# IMX7S_POWER.net
KiCad netlist of a schematic drawn in Altium Designer
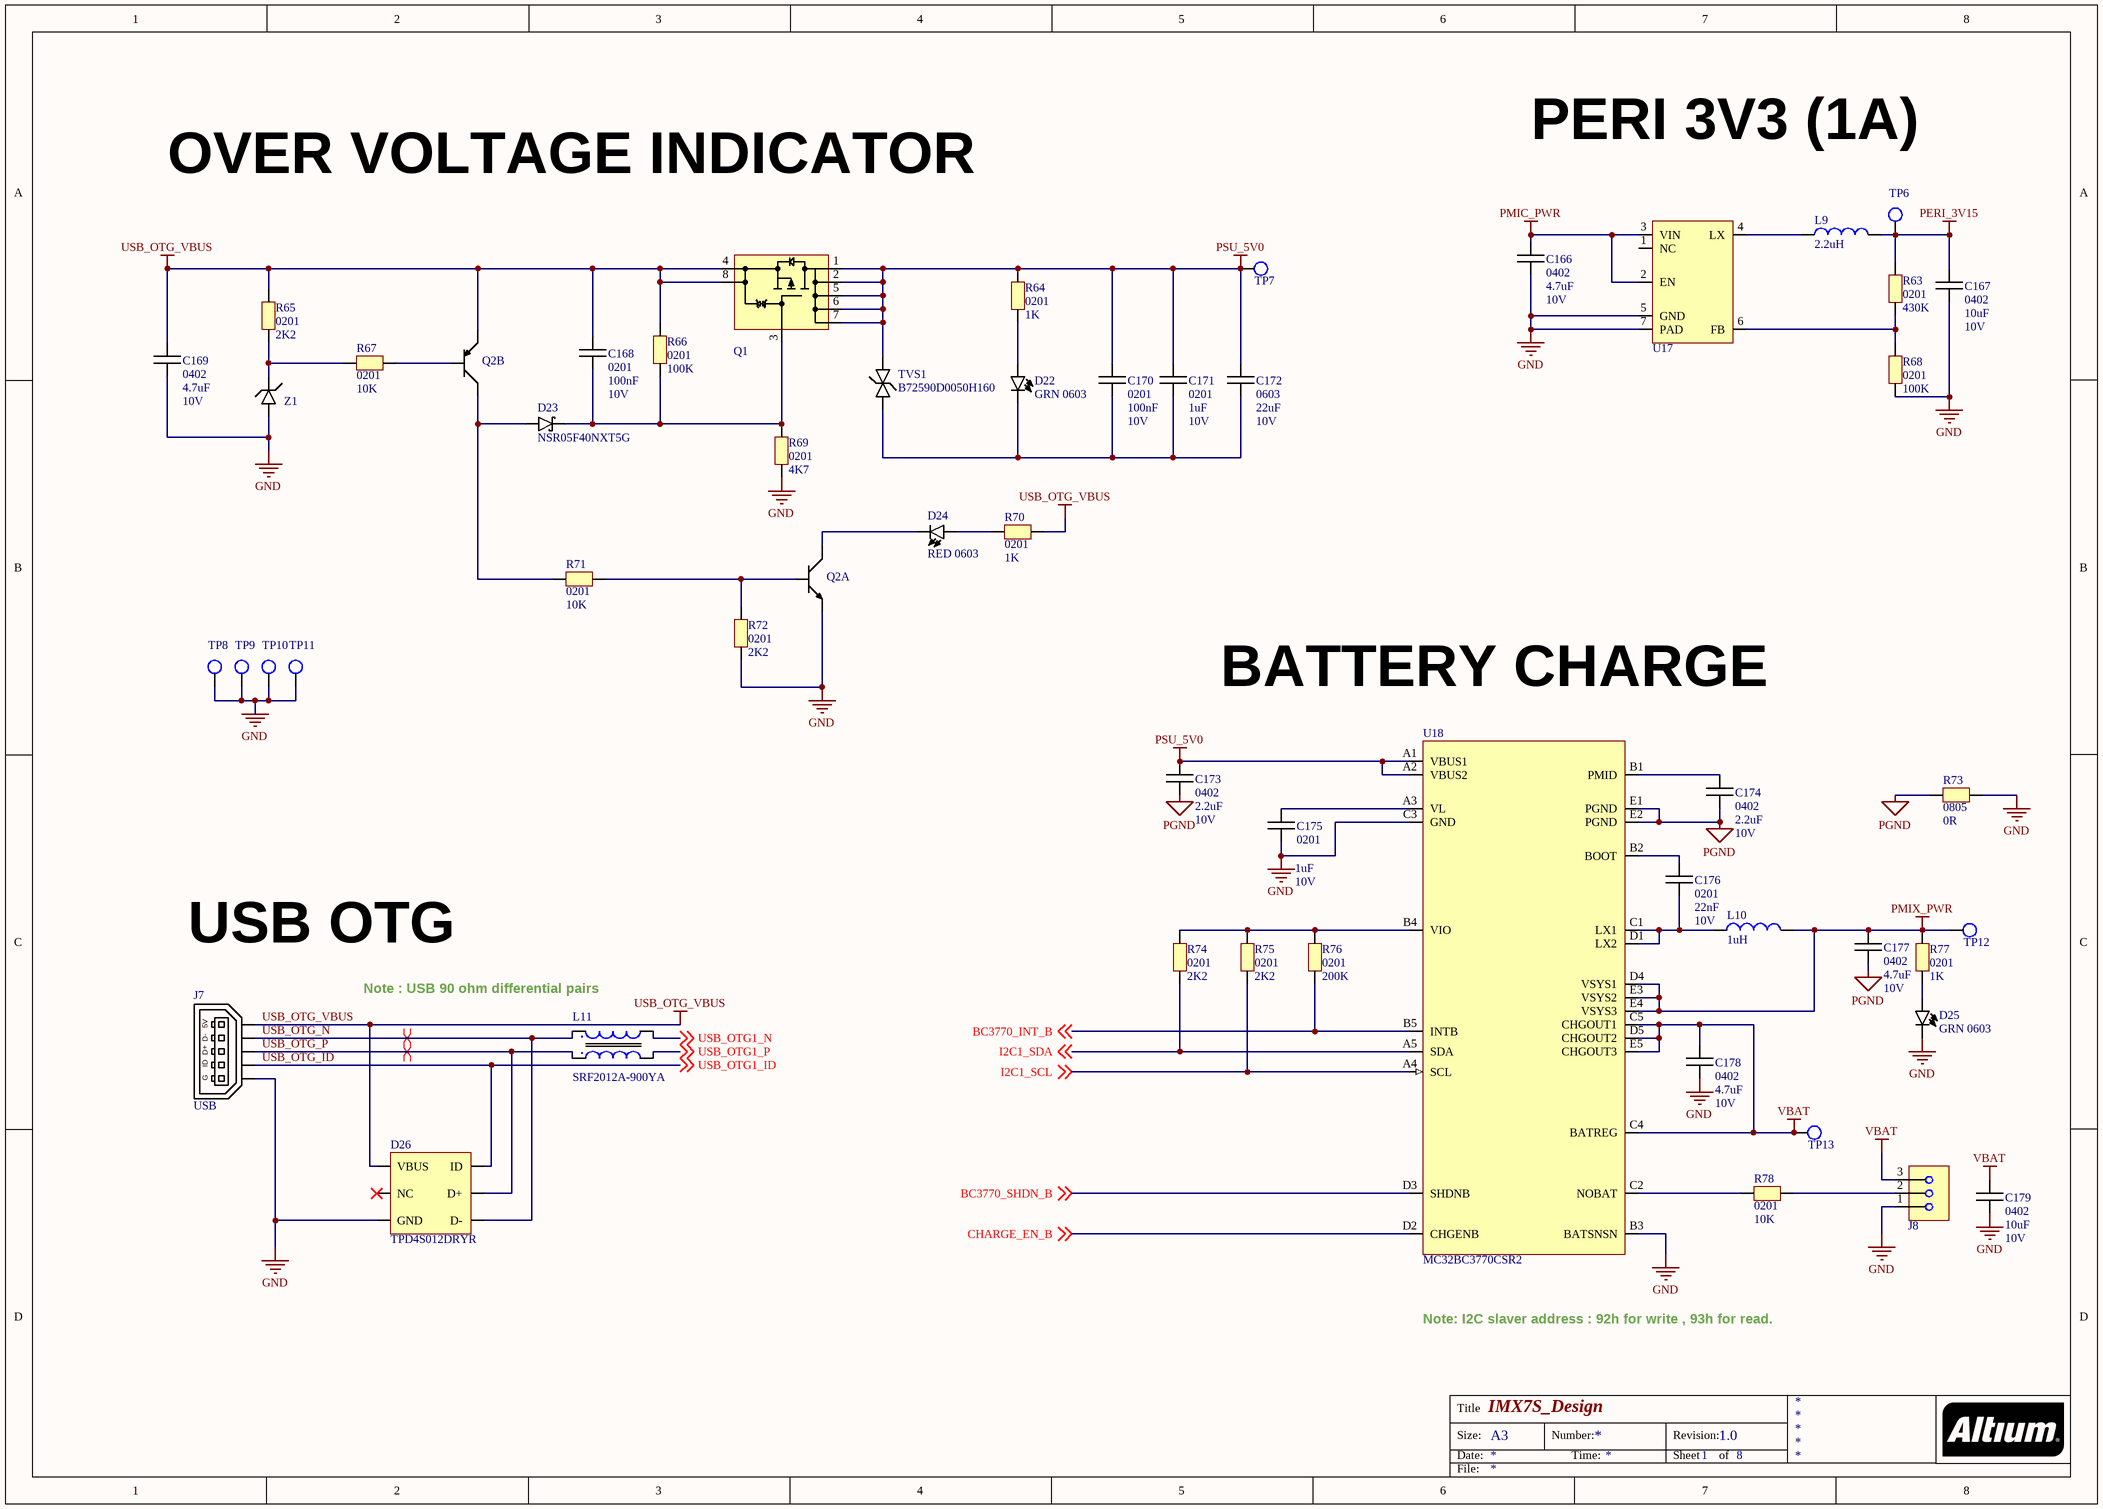
[diagram p0: IMX7S_POWER.SchDoc]

(export (version "E")
  (design (tool "Eeschema 10.0.6"))
  (components
    (comp (ref "C166")
      (value "4.7uF")
      (footprint "C0402")
      (fields (field (name "PACKAGE") "0402") (field (name "VOLTAGE") "10V") (field (name "Comment") "C0402"))
      (libsource (lib "Schlib_IMX7") (part "C0402"))
    )
    (comp (ref "C167")
      (value "10uF")
      (footprint "C0402")
      (description "Smd Multilayer Ceramic Capacitor, Grm Series, 10 F, 20%, X5r, 6.3 V, 0402 [1005 Metric]")
      (fields
        (field (name "PACKAGE") "0402")
        (field (name "VOLTAGE") "10V")
        (field (name "TOLERANCE") "20%")
        (field (name "Comment") "C0402")
      )
      (libsource (lib "Schlib_IMX7") (part "C0402"))
    )
    (comp (ref "C168")
      (value "100nF")
      (footprint "C0201")
      (fields
        (field (name "PACKAGE") "0201")
        (field (name "VOLTAGE") "10V")
        (field (name "TOLERANCE") "10%")
        (field (name "Comment") "C0201")
      )
      (libsource (lib "Schlib_IMX7") (part "C0201"))
    )
    (comp (ref "C169")
      (value "4.7uF")
      (footprint "C0402")
      (fields (field (name "PACKAGE") "0402") (field (name "VOLTAGE") "10V") (field (name "Comment") "C0402"))
      (libsource (lib "Schlib_IMX7") (part "C0402"))
    )
    (comp (ref "C170")
      (value "100nF")
      (footprint "C0201")
      (fields
        (field (name "PACKAGE") "0201")
        (field (name "VOLTAGE") "10V")
        (field (name "TOLERANCE") "10%")
        (field (name "Comment") "C0201")
      )
      (libsource (lib "Schlib_IMX7") (part "C0201"))
    )
    (comp (ref "C171")
      (value "1uF")
      (footprint "C0201")
      (description "CAP CER 1UF 6.3V X5R 0201")
      (fields
        (field (name "PACKAGE") "0201")
        (field (name "VOLTAGE") "10V")
        (field (name "TOLERANCE") "20%")
        (field (name "Comment") "C0201")
      )
      (libsource (lib "Schlib_IMX7") (part "C0201"))
    )
    (comp (ref "C172")
      (value "22uF")
      (footprint "C0603")
      (description "Cap Ceramic 22uF 6.3V X5R 20% SMD 0603 85C Paper T/R")
      (fields
        (field (name "PACKAGE") "0603")
        (field (name "VOLTAGE") "10V")
        (field (name "TOLERANCE") "20%")
        (field (name "Comment") "C0603")
      )
      (libsource (lib "Schlib_IMX7") (part "C0603"))
    )
    (comp (ref "C173")
      (value "2.2uF")
      (footprint "C0402")
      (fields
        (field (name "PACKAGE") "0402")
        (field (name "VOLTAGE") "10V")
        (field (name "TOLERANCE") "20%")
        (field (name "Comment") "C0402")
      )
      (libsource (lib "Schlib_IMX7") (part "C0402"))
    )
    (comp (ref "C174")
      (value "2.2uF")
      (footprint "C0402")
      (fields
        (field (name "PACKAGE") "0402")
        (field (name "VOLTAGE") "10V")
        (field (name "TOLERANCE") "20%")
        (field (name "Comment") "C0402")
      )
      (libsource (lib "Schlib_IMX7") (part "C0402"))
    )
    (comp (ref "C175")
      (value "1uF")
      (footprint "C0201")
      (description "CAP CER 1UF 6.3V X5R 0201")
      (fields
        (field (name "PACKAGE") "0201")
        (field (name "VOLTAGE") "10V")
        (field (name "TOLERANCE") "20%")
        (field (name "Comment") "C0201")
      )
      (libsource (lib "Schlib_IMX7") (part "C0201"))
    )
    (comp (ref "C176")
      (value "22nF")
      (footprint "C0201")
      (description "MULTICOMP - MC0201X223K6R3CT - CAP, 0.022µF, 6.3V, 10%, X5R, 0201")
      (fields
        (field (name "PACKAGE") "0201")
        (field (name "VOLTAGE") "10V")
        (field (name "TOLERANCE") "10%")
        (field (name "Comment") "C0201")
      )
      (libsource (lib "Schlib_IMX7") (part "C0201"))
    )
    (comp (ref "C177")
      (value "4.7uF")
      (footprint "C0402")
      (fields (field (name "PACKAGE") "0402") (field (name "VOLTAGE") "10V") (field (name "Comment") "C0402"))
      (libsource (lib "Schlib_IMX7") (part "C0402"))
    )
    (comp (ref "C178")
      (value "4.7uF")
      (footprint "C0402")
      (fields (field (name "PACKAGE") "0402") (field (name "VOLTAGE") "10V") (field (name "Comment") "C0402"))
      (libsource (lib "Schlib_IMX7") (part "C0402"))
    )
    (comp (ref "C179")
      (value "10uF")
      (footprint "C0402")
      (fields
        (field (name "PACKAGE") "0402")
        (field (name "VOLTAGE") "10V")
        (field (name "TOLERANCE") "20%")
        (field (name "Comment") "C0402")
      )
      (libsource (lib "Schlib_IMX7") (part "C0402"))
    )
    (comp (ref "D22") (value "GRN 0603") (footprint "D0603") (libsource (lib "Schlib_IMX7") (part "LED")))
    (comp (ref "D23")
      (value "NSR05F40NXT5G")
      (footprint "DSN2")
      (libsource (lib "Schlib_IMX7") (part "Shotky"))
    )
    (comp (ref "D24") (value "RED 0603") (footprint "D0603") (libsource (lib "Schlib_IMX7") (part "LED")))
    (comp (ref "D25") (value "GRN 0603") (footprint "D0603") (libsource (lib "Schlib_IMX7") (part "LED")))
    (comp (ref "D26")
      (value "TPD4S012DRYR")
      (footprint "SON6")
      (libsource (lib "Schlib_IMX7") (part "TPD4S012DRYR"))
    )
    (comp (ref "J7") (value "USB") (footprint "MICRO_USB") (libsource (lib "Schlib_IMX7") (part "MICRO_USB")))
    (comp (ref "J8")
      (value "JST_XH_3")
      (footprint "JST-XH")
      (libsource (lib "Schlib_IMX7") (part "JST_XH_3"))
    )
    (comp (ref "L9")
      (value "2.2uH")
      (footprint "SELF")
      (fields (field (name "TOLERANCE") "30%") (field (name "Comment") "Self"))
      (libsource (lib "Schlib_IMX7") (part "Self"))
    )
    (comp (ref "L10")
      (value "1uH")
      (footprint "R0402")
      (fields (field (name "TOLERANCE") "20%") (field (name "Comment") "Self"))
      (libsource (lib "Schlib_IMX7") (part "Self"))
    )
    (comp (ref "L11")
      (value "SRF2012A-900YA")
      (footprint "EMI_SP")
      (libsource (lib "Schlib_IMX7") (part "SRF2012A-900YA"))
    )
    (comp (ref "Q1")
      (value "FDMA530PZ")
      (footprint "MICROFET_2x2")
      (libsource (lib "Schlib_IMX7") (part "FDMA530PZ"))
    )
    (comp (ref "Q2")
      (value "HBDM60V600W-7")
      (footprint "SOT363")
      (libsource (lib "Schlib_IMX7") (part "HBDM60V600W-7"))
    )
    (comp (ref "R63")
      (value "430K")
      (footprint "R0201")
      (description "RES SMD 430K OHM 1% 1/20W 0201")
      (fields (field (name "PACKAGE") "0201") (field (name "VOLTAGE") "0V") (field (name "TOLERANCE") "1%"))
      (libsource (lib "") (part "R0201_1"))
    )
    (comp (ref "R64")
      (value "1K")
      (footprint "R0201")
      (fields
        (field (name "PACKAGE") "0201")
        (field (name "VOLTAGE") "0V")
        (field (name "TOLERANCE") "1%")
        (field (name "Comment") "R0201")
      )
      (libsource (lib "") (part "R0201_1"))
    )
    (comp (ref "R65")
      (value "2K2")
      (footprint "R0201")
      (description "MULTICOMP - MCRE000148 - RES, 2K2, 1%, 0.05W, 0201, THICK FILM")
      (fields (field (name "PACKAGE") "0201") (field (name "VOLTAGE") "0V") (field (name "TOLERANCE") "1%"))
      (libsource (lib "") (part "R0201_1"))
    )
    (comp (ref "R66")
      (value "100K")
      (footprint "R0201")
      (description "MULTICOMP - MCWR02X1003FAL - RES, 100K, 1%, 0.05W, THICK FILM")
      (fields (field (name "PACKAGE") "0201") (field (name "VOLTAGE") "0V") (field (name "TOLERANCE") "1%"))
      (libsource (lib "") (part "R0201_3"))
    )
    (comp (ref "R67")
      (value "10K")
      (footprint "R0201")
      (fields
        (field (name "PACKAGE") "0201")
        (field (name "VOLTAGE") "0V")
        (field (name "TOLERANCE") "1%")
        (field (name "Comment") "R0201")
      )
      (libsource (lib "") (part "R0201_2"))
    )
    (comp (ref "R68")
      (value "100K")
      (footprint "R0201")
      (description "MULTICOMP - MCWR02X1003FAL - RES, 100K, 1%, 0.05W, THICK FILM")
      (fields (field (name "PACKAGE") "0201") (field (name "VOLTAGE") "0V") (field (name "TOLERANCE") "1%"))
      (libsource (lib "") (part "R0201_1"))
    )
    (comp (ref "R69")
      (value "4K7")
      (footprint "R0201")
      (description "RES SMD 4.7K OHM 1% 1/20W 0201")
      (fields (field (name "PACKAGE") "0201") (field (name "VOLTAGE") "0V") (field (name "TOLERANCE") "1%"))
      (libsource (lib "") (part "R0201_3"))
    )
    (comp (ref "R70")
      (value "1K")
      (footprint "R0201")
      (fields
        (field (name "PACKAGE") "0201")
        (field (name "VOLTAGE") "0V")
        (field (name "TOLERANCE") "1%")
        (field (name "Comment") "R0201")
      )
      (libsource (lib "Schlib_IMX7") (part "R0201"))
    )
    (comp (ref "R71")
      (value "10K")
      (footprint "R0201")
      (fields
        (field (name "PACKAGE") "0201")
        (field (name "VOLTAGE") "0V")
        (field (name "TOLERANCE") "1%")
        (field (name "Comment") "R0201")
      )
      (libsource (lib "") (part "R0201_2"))
    )
    (comp (ref "R72")
      (value "2K2")
      (footprint "R0201")
      (description "MULTICOMP - MCRE000148 - RES, 2K2, 1%, 0.05W, 0201, THICK FILM")
      (fields (field (name "PACKAGE") "0201") (field (name "VOLTAGE") "0V") (field (name "TOLERANCE") "1%"))
      (libsource (lib "") (part "R0201_1"))
    )
    (comp (ref "R73")
      (value "0R")
      (footprint "R0805")
      (description "RESISTOR, THICK FILM, JUMPER, 0 OHM, 125mW, 1%")
      (fields (field (name "PACKAGE") "0805") (field (name "VOLTAGE") "0V") (field (name "TOLERANCE") "1%"))
      (libsource (lib "Schlib_IMX7") (part "R0805"))
    )
    (comp (ref "R74")
      (value "2K2")
      (footprint "R0201")
      (description "MULTICOMP - MCRE000148 - RES, 2K2, 1%, 0.05W, 0201, THICK FILM")
      (fields (field (name "PACKAGE") "0201") (field (name "VOLTAGE") "0V") (field (name "TOLERANCE") "1%"))
      (libsource (lib "") (part "R0201_1"))
    )
    (comp (ref "R75")
      (value "2K2")
      (footprint "R0201")
      (description "MULTICOMP - MCRE000148 - RES, 2K2, 1%, 0.05W, 0201, THICK FILM")
      (fields (field (name "PACKAGE") "0201") (field (name "VOLTAGE") "0V") (field (name "TOLERANCE") "1%"))
      (libsource (lib "") (part "R0201_1"))
    )
    (comp (ref "R76")
      (value "200K")
      (footprint "R0201")
      (description "MULTICOMP - MCRE000195 - RES COUCHE EPAISSE 200K 1% 0.05W 0201")
      (fields (field (name "PACKAGE") "0201") (field (name "VOLTAGE") "0V") (field (name "TOLERANCE") "1%"))
      (libsource (lib "") (part "R0201_1"))
    )
    (comp (ref "R77")
      (value "1K")
      (footprint "R0201")
      (fields
        (field (name "PACKAGE") "0201")
        (field (name "VOLTAGE") "0V")
        (field (name "TOLERANCE") "1%")
        (field (name "Comment") "R0201")
      )
      (libsource (lib "") (part "R0201_1"))
    )
    (comp (ref "R78")
      (value "10K")
      (footprint "R0201")
      (fields
        (field (name "PACKAGE") "0201")
        (field (name "VOLTAGE") "0V")
        (field (name "TOLERANCE") "1%")
        (field (name "Comment") "R0201")
      )
      (libsource (lib "") (part "R0201_2"))
    )
    (comp (ref "TP6")
      (value "TestPoint")
      (footprint "TESTPOINT")
      (libsource (lib "Schlib_IMX7") (part "TestPoint"))
    )
    (comp (ref "TP7")
      (value "TestPoint")
      (footprint "TESTPOINT")
      (libsource (lib "Schlib_IMX7") (part "TestPoint"))
    )
    (comp (ref "TP8")
      (value "TestPoint")
      (footprint "TESTPOINT")
      (libsource (lib "Schlib_IMX7") (part "TestPoint"))
    )
    (comp (ref "TP9")
      (value "TestPoint")
      (footprint "TESTPOINT")
      (libsource (lib "Schlib_IMX7") (part "TestPoint"))
    )
    (comp (ref "TP10")
      (value "TestPoint")
      (footprint "TESTPOINT")
      (libsource (lib "Schlib_IMX7") (part "TestPoint"))
    )
    (comp (ref "TP11")
      (value "TestPoint")
      (footprint "TESTPOINT")
      (libsource (lib "Schlib_IMX7") (part "TestPoint"))
    )
    (comp (ref "TP12")
      (value "TestPoint")
      (footprint "TESTPOINT")
      (libsource (lib "Schlib_IMX7") (part "TestPoint"))
    )
    (comp (ref "TP13")
      (value "TestPoint")
      (footprint "TESTPOINT")
      (libsource (lib "Schlib_IMX7") (part "TestPoint"))
    )
    (comp (ref "TVS1")
      (value "B72590D0050H160")
      (footprint "R0402")
      (libsource (lib "Schlib_IMX7") (part "B72590D0050H160"))
    )
    (comp (ref "U17")
      (value "AP3417CDNTR-G1")
      (footprint "DFN2020")
      (libsource (lib "Schlib_IMX7") (part "AP3417CDNTR-G1"))
    )
    (comp (ref "U18")
      (value "MC32BC3770CSR2")
      (footprint "BGA25x5")
      (libsource (lib "Schlib_IMX7") (part "MC32BC3770CSR2"))
    )
    (comp (ref "Z1")
      (value "Zener")
      (footprint "Zener")
      (fields (field (name "TOLERANCE") "2%"))
      (libsource (lib "Schlib_IMX7") (part "Zener"))
    )
  )
  (nets
    (net (code "1") (name "/USB_OTG_N") (class "Default")
      (node (ref "D26") (pin "2") (pinfunction "D-_2") (pintype "passive"))
      (node (ref "J7") (pin "2") (pinfunction "D-_2") (pintype "passive"))
      (node (ref "L11") (pin "1") (pinfunction "1_1") (pintype "passive"))
    )
    (net (code "2") (name "/USB_OTG_P") (class "Default")
      (node (ref "D26") (pin "1") (pinfunction "D+_1") (pintype "passive"))
      (node (ref "J7") (pin "3") (pinfunction "D+_3") (pintype "passive"))
      (node (ref "L11") (pin "4") (pinfunction "4_4") (pintype "passive"))
    )
    (net (code "3") (name "BC3770_INT_B") (class "Default")
      (node (ref "R76") (pin "1") (pinfunction "1_1") (pintype "passive"))
      (node (ref "U18") (pin "B5") (pinfunction "INTB_B5") (pintype "passive"))
    )
    (net (code "4") (name "BC3770_SHDN_B") (class "Default")
      (node (ref "U18") (pin "D3") (pinfunction "SHDNB_D3") (pintype "passive"))
    )
    (net (code "5") (name "CHARGE_EN_B") (class "Default")
      (node (ref "U18") (pin "D2") (pinfunction "CHGENB_D2") (pintype "passive"))
    )
    (net (code "6") (name "GND") (class "Default")
      (node (ref "C166") (pin "2") (pinfunction "2_2") (pintype "passive"))
      (node (ref "C167") (pin "2") (pinfunction "2_2") (pintype "passive"))
      (node (ref "C169") (pin "1") (pinfunction "1_1") (pintype "passive"))
      (node (ref "C175") (pin "1") (pinfunction "1_1") (pintype "passive"))
      (node (ref "C178") (pin "2") (pinfunction "2_2") (pintype "passive"))
      (node (ref "C179") (pin "2") (pinfunction "2_2") (pintype "passive"))
      (node (ref "D25") (pin "2") (pinfunction "K_2") (pintype "passive"))
      (node (ref "D26") (pin "4") (pinfunction "GND_4") (pintype "passive"))
      (node (ref "J7") (pin "5") (pinfunction "GND_5") (pintype "passive"))
      (node (ref "J8") (pin "1") (pintype "passive"))
      (node (ref "Q2") (pin "5") (pinfunction "EQ1_5") (pintype "passive"))
      (node (ref "R68") (pin "1") (pinfunction "1_1") (pintype "passive"))
      (node (ref "R69") (pin "2") (pinfunction "2_2") (pintype "passive"))
      (node (ref "R72") (pin "1") (pinfunction "1_1") (pintype "passive"))
      (node (ref "R73") (pin "2") (pinfunction "2_2") (pintype "passive"))
      (node (ref "TP10") (pin "1") (pinfunction "1_1") (pintype "passive"))
      (node (ref "TP11") (pin "1") (pinfunction "1_1") (pintype "passive"))
      (node (ref "TP8") (pin "1") (pinfunction "1_1") (pintype "passive"))
      (node (ref "TP9") (pin "1") (pinfunction "1_1") (pintype "passive"))
      (node (ref "U17") (pin "5") (pinfunction "GND_5") (pintype "passive"))
      (node (ref "U17") (pin "7") (pinfunction "PAD_7") (pintype "passive"))
      (node (ref "U18") (pin "B3") (pinfunction "BATSNSN_B3") (pintype "passive"))
      (node (ref "U18") (pin "C3") (pinfunction "GND_C3") (pintype "passive"))
      (node (ref "Z1") (pin "1") (pinfunction "A_1") (pintype "passive"))
    )
    (net (code "7") (name "I2C1_SCL") (class "Default")
      (node (ref "R75") (pin "1") (pinfunction "1_1") (pintype "passive"))
      (node (ref "U18") (pin "A4") (pinfunction "SCL_A4") (pintype "input"))
    )
    (net (code "8") (name "I2C1_SDA") (class "Default")
      (node (ref "R74") (pin "1") (pinfunction "1_1") (pintype "passive"))
      (node (ref "U18") (pin "A5") (pinfunction "SDA_A5") (pintype "passive"))
    )
    (net (code "9") (name "Net-(D22-A)") (class "Default")
      (node (ref "D22") (pin "1") (pinfunction "A_1") (pintype "passive"))
      (node (ref "R64") (pin "1") (pinfunction "1_1") (pintype "passive"))
    )
    (net (code "10") (name "Net-(D22-K)") (class "Default")
      (node (ref "C170") (pin "1") (pinfunction "1_1") (pintype "passive"))
      (node (ref "C171") (pin "1") (pinfunction "1_1") (pintype "passive"))
      (node (ref "C172") (pin "1") (pinfunction "1_1") (pintype "passive"))
      (node (ref "D22") (pin "2") (pinfunction "K_2") (pintype "passive"))
      (node (ref "TVS1") (pin "1") (pinfunction "1_1") (pintype "passive"))
    )
    (net (code "11") (name "Net-(D23-A)") (class "Default")
      (node (ref "D23") (pin "2") (pinfunction "A_2") (pintype "passive"))
      (node (ref "Q2") (pin "3") (pinfunction "CQ2_3") (pintype "passive"))
      (node (ref "R71") (pin "2") (pinfunction "2_2") (pintype "passive"))
    )
    (net (code "12") (name "Net-(D23-K)") (class "Default")
      (node (ref "C168") (pin "1") (pinfunction "1_1") (pintype "passive"))
      (node (ref "D23") (pin "1") (pinfunction "K_1") (pintype "passive"))
      (node (ref "Q1") (pin "3") (pintype "passive"))
      (node (ref "R66") (pin "2") (pinfunction "2_2") (pintype "passive"))
      (node (ref "R69") (pin "1") (pinfunction "1_1") (pintype "passive"))
    )
    (net (code "13") (name "Net-(D24-A)") (class "Default")
      (node (ref "D24") (pin "1") (pinfunction "A_1") (pintype "passive"))
      (node (ref "R70") (pin "1") (pinfunction "1_1") (pintype "passive"))
    )
    (net (code "14") (name "Net-(D24-K)") (class "Default")
      (node (ref "D24") (pin "2") (pinfunction "K_2") (pintype "passive"))
      (node (ref "Q2") (pin "6") (pinfunction "CQ1_6") (pintype "passive"))
    )
    (net (code "15") (name "Net-(D25-A)") (class "Default")
      (node (ref "D25") (pin "1") (pinfunction "A_1") (pintype "passive"))
      (node (ref "R77") (pin "1") (pinfunction "1_1") (pintype "passive"))
    )
    (net (code "16") (name "Net-(J8-Pad2)") (class "Default")
      (node (ref "J8") (pin "2") (pintype "passive"))
      (node (ref "R78") (pin "1") (pinfunction "1_1") (pintype "passive"))
    )
    (net (code "17") (name "Net-(Q2A-QB1)") (class "Default")
      (node (ref "Q2") (pin "1") (pinfunction "QB1_1") (pintype "passive"))
      (node (ref "R71") (pin "1") (pinfunction "1_1") (pintype "passive"))
      (node (ref "R72") (pin "2") (pinfunction "2_2") (pintype "passive"))
    )
    (net (code "18") (name "Net-(Q2B-QB2)") (class "Default")
      (node (ref "Q2") (pin "2") (pinfunction "QB2_2") (pintype "passive"))
      (node (ref "R67") (pin "1") (pinfunction "1_1") (pintype "passive"))
    )
    (net (code "19") (name "Net-(U17-FB)") (class "Default")
      (node (ref "R63") (pin "1") (pinfunction "1_1") (pintype "passive"))
      (node (ref "R68") (pin "2") (pinfunction "2_2") (pintype "passive"))
      (node (ref "U17") (pin "6") (pinfunction "FB_6") (pintype "passive"))
    )
    (net (code "20") (name "Net-(U17-LX)") (class "Default")
      (node (ref "L9") (pin "1") (pintype "passive"))
      (node (ref "U17") (pin "4") (pinfunction "LX_4") (pintype "passive"))
    )
    (net (code "21") (name "Net-(U18-BOOT)") (class "Default")
      (node (ref "C176") (pin "2") (pinfunction "2_2") (pintype "passive"))
      (node (ref "U18") (pin "B2") (pinfunction "BOOT_B2") (pintype "passive"))
    )
    (net (code "22") (name "Net-(U18-LX1)") (class "Default")
      (node (ref "C176") (pin "1") (pinfunction "1_1") (pintype "passive"))
      (node (ref "L10") (pin "1") (pintype "passive"))
      (node (ref "U18") (pin "C1") (pinfunction "LX1_C1") (pintype "passive"))
      (node (ref "U18") (pin "D1") (pinfunction "LX2_D1") (pintype "passive"))
    )
    (net (code "23") (name "Net-(U18-NOBAT)") (class "Default")
      (node (ref "R78") (pin "2") (pinfunction "2_2") (pintype "passive"))
      (node (ref "U18") (pin "C2") (pinfunction "NOBAT_C2") (pintype "passive"))
    )
    (net (code "24") (name "Net-(U18-PMID)") (class "Default")
      (node (ref "C174") (pin "2") (pinfunction "2_2") (pintype "passive"))
      (node (ref "U18") (pin "B1") (pinfunction "PMID_B1") (pintype "passive"))
    )
    (net (code "25") (name "Net-(U18-VIO)") (class "Default")
      (node (ref "R74") (pin "2") (pinfunction "2_2") (pintype "passive"))
      (node (ref "R75") (pin "2") (pinfunction "2_2") (pintype "passive"))
      (node (ref "R76") (pin "2") (pinfunction "2_2") (pintype "passive"))
      (node (ref "U18") (pin "B4") (pinfunction "VIO_B4") (pintype "passive"))
    )
    (net (code "26") (name "Net-(U18-VL)") (class "Default")
      (node (ref "C175") (pin "2") (pinfunction "2_2") (pintype "passive"))
      (node (ref "U18") (pin "A3") (pinfunction "VL_A3") (pintype "passive"))
    )
    (net (code "27") (name "Net-(Z1-K)") (class "Default")
      (node (ref "R65") (pin "1") (pinfunction "1_1") (pintype "passive"))
      (node (ref "R67") (pin "2") (pinfunction "2_2") (pintype "passive"))
      (node (ref "Z1") (pin "2") (pinfunction "K_2") (pintype "passive"))
    )
    (net (code "28") (name "PERI_3V15") (class "Default")
      (node (ref "C167") (pin "1") (pinfunction "1_1") (pintype "passive"))
      (node (ref "L9") (pin "2") (pintype "passive"))
      (node (ref "R63") (pin "2") (pinfunction "2_2") (pintype "passive"))
      (node (ref "TP6") (pin "1") (pinfunction "1_1") (pintype "passive"))
    )
    (net (code "29") (name "PGND") (class "Default")
      (node (ref "C173") (pin "1") (pinfunction "1_1") (pintype "passive"))
      (node (ref "C174") (pin "1") (pinfunction "1_1") (pintype "passive"))
      (node (ref "C177") (pin "2") (pinfunction "2_2") (pintype "passive"))
      (node (ref "R73") (pin "1") (pinfunction "1_1") (pintype "passive"))
      (node (ref "U18") (pin "E1") (pinfunction "PGND_E1") (pintype "passive"))
      (node (ref "U18") (pin "E2") (pinfunction "PGND_E2") (pintype "passive"))
    )
    (net (code "30") (name "PMIC_PWR") (class "Default")
      (node (ref "C166") (pin "1") (pinfunction "1_1") (pintype "passive"))
      (node (ref "U17") (pin "2") (pinfunction "EN_2") (pintype "passive"))
      (node (ref "U17") (pin "3") (pinfunction "VIN_3") (pintype "passive"))
    )
    (net (code "31") (name "PMIX_PWR") (class "Default")
      (node (ref "C177") (pin "1") (pinfunction "1_1") (pintype "passive"))
      (node (ref "L10") (pin "2") (pintype "passive"))
      (node (ref "R77") (pin "2") (pinfunction "2_2") (pintype "passive"))
      (node (ref "TP12") (pin "1") (pinfunction "1_1") (pintype "passive"))
      (node (ref "U18") (pin "D4") (pinfunction "VSYS1_D4") (pintype "passive"))
      (node (ref "U18") (pin "E3") (pinfunction "VSYS2_E3") (pintype "passive"))
      (node (ref "U18") (pin "E4") (pinfunction "VSYS3_E4") (pintype "passive"))
    )
    (net (code "32") (name "PSU_5V0") (class "Default")
      (node (ref "C170") (pin "2") (pinfunction "2_2") (pintype "passive"))
      (node (ref "C171") (pin "2") (pinfunction "2_2") (pintype "passive"))
      (node (ref "C172") (pin "2") (pinfunction "2_2") (pintype "passive"))
      (node (ref "C173") (pin "2") (pinfunction "2_2") (pintype "passive"))
      (node (ref "Q1") (pin "1") (pintype "passive"))
      (node (ref "Q1") (pin "2") (pintype "passive"))
      (node (ref "Q1") (pin "5") (pintype "passive"))
      (node (ref "Q1") (pin "6") (pintype "passive"))
      (node (ref "Q1") (pin "7") (pintype "passive"))
      (node (ref "R64") (pin "2") (pinfunction "2_2") (pintype "passive"))
      (node (ref "TP7") (pin "1") (pinfunction "1_1") (pintype "passive"))
      (node (ref "TVS1") (pin "2") (pinfunction "2_2") (pintype "passive"))
      (node (ref "U18") (pin "A1") (pinfunction "VBUS1_A1") (pintype "passive"))
      (node (ref "U18") (pin "A2") (pinfunction "VBUS2_A2") (pintype "passive"))
    )
    (net (code "33") (name "USB_OTG1_ID") (class "Default")
      (node (ref "D26") (pin "3") (pinfunction "ID_3") (pintype "passive"))
      (node (ref "J7") (pin "4") (pinfunction "ID_4") (pintype "passive"))
    )
    (net (code "34") (name "USB_OTG1_N") (class "Default")
      (node (ref "L11") (pin "2") (pinfunction "2_2") (pintype "passive"))
    )
    (net (code "35") (name "USB_OTG1_P") (class "Default")
      (node (ref "L11") (pin "3") (pinfunction "3_3") (pintype "passive"))
    )
    (net (code "36") (name "USB_OTG_VBUS") (class "Default")
      (node (ref "C168") (pin "2") (pinfunction "2_2") (pintype "passive"))
      (node (ref "C169") (pin "2") (pinfunction "2_2") (pintype "passive"))
      (node (ref "D26") (pin "6") (pinfunction "VBUS_6") (pintype "passive"))
      (node (ref "J7") (pin "1") (pinfunction "5V_1") (pintype "passive"))
      (node (ref "Q1") (pin "4") (pintype "passive"))
      (node (ref "Q1") (pin "8") (pintype "passive"))
      (node (ref "Q2") (pin "4") (pinfunction "EQ2_4") (pintype "passive"))
      (node (ref "R65") (pin "2") (pinfunction "2_2") (pintype "passive"))
      (node (ref "R66") (pin "1") (pinfunction "1_1") (pintype "passive"))
      (node (ref "R70") (pin "2") (pinfunction "2_2") (pintype "passive"))
    )
    (net (code "37") (name "VBAT") (class "Default")
      (node (ref "C178") (pin "1") (pinfunction "1_1") (pintype "passive"))
      (node (ref "C179") (pin "1") (pinfunction "1_1") (pintype "passive"))
      (node (ref "J8") (pin "3") (pintype "passive"))
      (node (ref "TP13") (pin "1") (pinfunction "1_1") (pintype "passive"))
      (node (ref "U18") (pin "C4") (pinfunction "BATREG_C4") (pintype "passive"))
      (node (ref "U18") (pin "C5") (pinfunction "CHGOUT1_C5") (pintype "passive"))
      (node (ref "U18") (pin "D5") (pinfunction "CHGOUT2_D5") (pintype "passive"))
      (node (ref "U18") (pin "E5") (pinfunction "CHGOUT3_E5") (pintype "passive"))
    )
    (net (code "38") (name "unconnected-(D26-NC-Pad5)") (class "Default")
      (node (ref "D26") (pin "5") (pinfunction "NC_5") (pintype "passive+no_connect"))
    )
    (net (code "39") (name "unconnected-(U17-NC-Pad1)") (class "Default")
      (node (ref "U17") (pin "1") (pinfunction "NC_1") (pintype "passive"))
    )
  )
)
